# EMS_esp32_LoRa.net
KiCad netlist of a schematic drawn in EAGLE
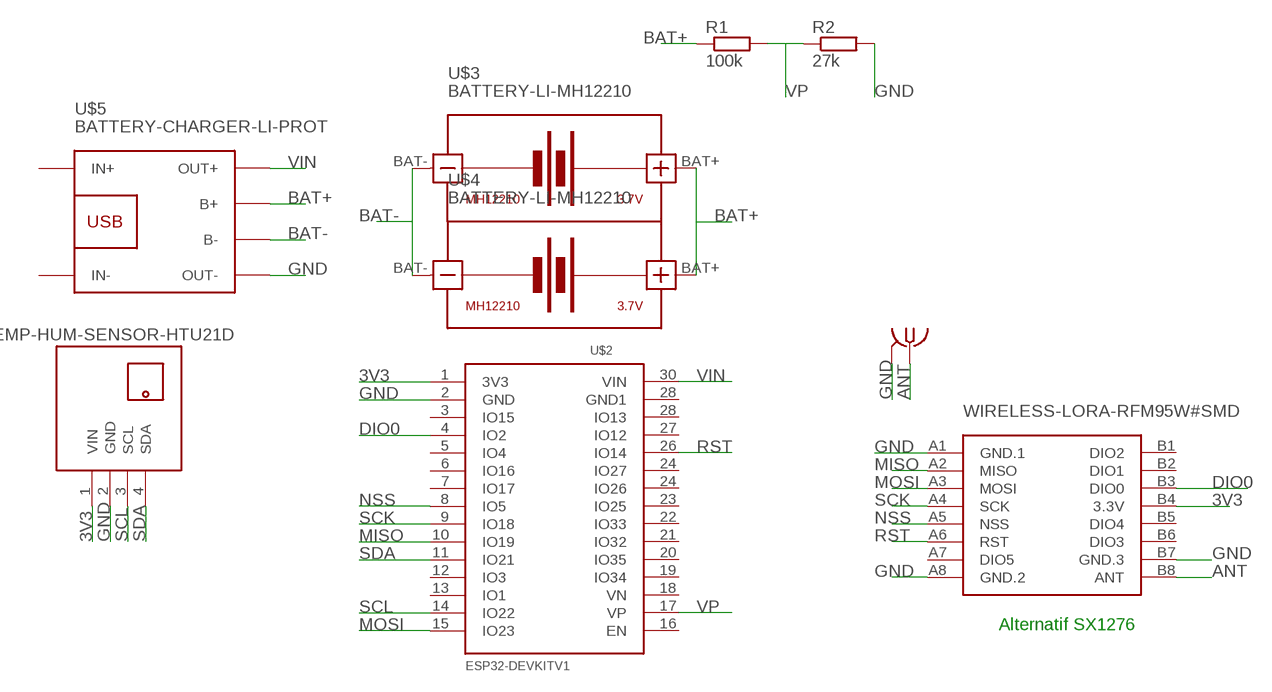
[diagram p0: schematic, sheet 1]

(export (version "E")
  (design (tool "Eeschema 10.0.6"))
  (components
    (comp (ref "R1")
      (value "100k")
      (footprint "eagle-import:0204_7")
      (libsource (lib "eagle-import") (part "R-EU_0204/7"))
    )
    (comp (ref "R2")
      (value "27k")
      (footprint "eagle-import:0204_7")
      (libsource (lib "eagle-import") (part "R-EU_0204/7"))
    )
    (comp (ref "U$1")
      (value "WIRELESS-LORA-RFM95W#SMD")
      (footprint "eagle-import:WIRELESS-LORA-RFM95W#SMD")
      (libsource (lib "eagle-import") (part "WIRELESS-LORA-RFM95W#SMD"))
    )
    (comp (ref "U$2")
      (value "ESP32DEVKITV1")
      (footprint "eagle-import:ESP32-DEVKITV1")
      (libsource (lib "eagle-import") (part "ESP32DEVKITV1"))
    )
    (comp (ref "U$3")
      (value "BATTERY-LI-MH12210")
      (footprint "eagle-import:BATTERY-LI-MH12210")
      (libsource (lib "eagle-import") (part "BATTERY-LI-MH12210"))
    )
    (comp (ref "U$4")
      (value "BATTERY-LI-MH12210")
      (footprint "eagle-import:BATTERY-LI-MH12210")
      (libsource (lib "eagle-import") (part "BATTERY-LI-MH12210"))
    )
    (comp (ref "U$5")
      (value "BATTERY-CHARGER-LI-PROT")
      (footprint "eagle-import:BATTERY-CHARGER-LI-PROT")
      (libsource (lib "eagle-import") (part "BATTERY-CHARGER-LI-PROT"))
    )
    (comp (ref "U$6")
      (value "TEMP-HUM-SENSOR-HTU21D")
      (footprint "eagle-import:TEMP-HUM-SENSOR-HTU21D")
      (libsource (lib "eagle-import") (part "TEMP-HUM-SENSOR-HTU21D"))
    )
    (comp (ref "X1")
      (value "SMA-142-0701-801/806")
      (footprint "eagle-import:J502-ND-142-0701-801_806")
      (fields (field (name "MF") "JOHNSON COMPONENTS") (field (name "MPN") "142-0701-801"))
      (libsource (lib "eagle-import") (part "SMA-142-0701-801/806"))
    )
  )
  (nets
    (net (code "1") (name "/3V3") (class "Default")
      (node (ref "U$1") (pin "B4") (pinfunction "3.3V_B4") (pintype "power_in"))
      (node (ref "U$2") (pin "1") (pinfunction "3V3_1") (pintype "bidirectional"))
      (node (ref "U$6") (pin "1") (pinfunction "VIN_1") (pintype "power_in"))
    )
    (net (code "2") (name "/ANT") (class "Default")
      (node (ref "U$1") (pin "B8") (pinfunction "ANT_B8") (pintype "passive"))
      (node (ref "X1") (pin "1") (pinfunction "1_1") (pintype "passive"))
    )
    (net (code "3") (name "/BAT+") (class "Default")
      (node (ref "R1") (pin "1") (pinfunction "1_1") (pintype "passive"))
      (node (ref "U$3") (pin "BAT+") (pinfunction "BAT+_BAT+") (pintype "power_in"))
      (node (ref "U$4") (pin "BAT+") (pinfunction "BAT+_BAT+") (pintype "power_in"))
      (node (ref "U$5") (pin "B+") (pinfunction "B+_B+") (pintype "bidirectional"))
    )
    (net (code "4") (name "/BAT-") (class "Default")
      (node (ref "U$3") (pin "BAT-") (pinfunction "BAT-_BAT-") (pintype "power_in"))
      (node (ref "U$4") (pin "BAT-") (pinfunction "BAT-_BAT-") (pintype "power_in"))
      (node (ref "U$5") (pin "B-") (pinfunction "B-_B-") (pintype "bidirectional"))
    )
    (net (code "5") (name "/DIO0") (class "Default")
      (node (ref "U$1") (pin "B3") (pinfunction "DIO0_B3") (pintype "bidirectional"))
      (node (ref "U$2") (pin "4") (pinfunction "IO2_4") (pintype "bidirectional"))
    )
    (net (code "6") (name "/GND") (class "Default")
      (node (ref "R2") (pin "2") (pinfunction "2_2") (pintype "passive"))
      (node (ref "U$1") (pin "A1") (pinfunction "GND.1_A1") (pintype "power_in"))
      (node (ref "U$1") (pin "A8") (pinfunction "GND.2_A8") (pintype "power_in"))
      (node (ref "U$1") (pin "B7") (pinfunction "GND.3_B7") (pintype "power_in"))
      (node (ref "U$2") (pin "2") (pinfunction "GND_2") (pintype "bidirectional"))
      (node (ref "U$5") (pin "OUT-") (pinfunction "OUT-_OUT-") (pintype "bidirectional"))
      (node (ref "U$6") (pin "2") (pinfunction "GND_2") (pintype "power_in"))
      (node (ref "X1") (pin "G@1") (pinfunction "2_G@1") (pintype "passive"))
      (node (ref "X1") (pin "G@2") (pinfunction "2_G@2") (pintype "passive"))
      (node (ref "X1") (pin "G@3") (pinfunction "2_G@3") (pintype "passive"))
      (node (ref "X1") (pin "G@4") (pinfunction "2_G@4") (pintype "passive"))
    )
    (net (code "7") (name "/MISO") (class "Default")
      (node (ref "U$1") (pin "A2") (pinfunction "MISO_A2") (pintype "bidirectional"))
      (node (ref "U$2") (pin "10") (pinfunction "IO19_10") (pintype "bidirectional"))
    )
    (net (code "8") (name "/MOSI") (class "Default")
      (node (ref "U$1") (pin "A3") (pinfunction "MOSI_A3") (pintype "bidirectional"))
      (node (ref "U$2") (pin "15") (pinfunction "IO23_15") (pintype "bidirectional"))
    )
    (net (code "9") (name "/NSS") (class "Default")
      (node (ref "U$1") (pin "A5") (pinfunction "NSS_A5") (pintype "bidirectional"))
      (node (ref "U$2") (pin "8") (pinfunction "IO5_8") (pintype "bidirectional"))
    )
    (net (code "10") (name "/RST") (class "Default")
      (node (ref "U$1") (pin "A6") (pinfunction "RST_A6") (pintype "bidirectional"))
      (node (ref "U$2") (pin "26") (pinfunction "IO14_26") (pintype "bidirectional"))
    )
    (net (code "11") (name "/SCK") (class "Default")
      (node (ref "U$1") (pin "A4") (pinfunction "SCK_A4") (pintype "bidirectional"))
      (node (ref "U$2") (pin "9") (pinfunction "IO18_9") (pintype "bidirectional"))
    )
    (net (code "12") (name "/SCL") (class "Default")
      (node (ref "U$2") (pin "14") (pinfunction "IO22_14") (pintype "bidirectional"))
      (node (ref "U$6") (pin "3") (pinfunction "SCL_3") (pintype "bidirectional"))
    )
    (net (code "13") (name "/SDA") (class "Default")
      (node (ref "U$2") (pin "11") (pinfunction "IO21_11") (pintype "bidirectional"))
      (node (ref "U$6") (pin "4") (pinfunction "SDA_4") (pintype "bidirectional"))
    )
    (net (code "14") (name "/VIN") (class "Default")
      (node (ref "U$2") (pin "30") (pinfunction "VIN_30") (pintype "bidirectional"))
      (node (ref "U$5") (pin "OUT+") (pinfunction "OUT+_OUT+") (pintype "bidirectional"))
    )
    (net (code "15") (name "/VP") (class "Default")
      (node (ref "R1") (pin "2") (pinfunction "2_2") (pintype "passive"))
      (node (ref "R2") (pin "1") (pinfunction "1_1") (pintype "passive"))
      (node (ref "U$2") (pin "17") (pinfunction "VP_17") (pintype "bidirectional"))
    )
    (net (code "16") (name "unconnected-(U$1-DIO1-PadB2)") (class "Default")
      (node (ref "U$1") (pin "B2") (pinfunction "DIO1_B2") (pintype "bidirectional"))
    )
    (net (code "17") (name "unconnected-(U$1-DIO2-PadB1)") (class "Default")
      (node (ref "U$1") (pin "B1") (pinfunction "DIO2_B1") (pintype "bidirectional"))
    )
    (net (code "18") (name "unconnected-(U$1-DIO3-PadB6)") (class "Default")
      (node (ref "U$1") (pin "B6") (pinfunction "DIO3_B6") (pintype "bidirectional"))
    )
    (net (code "19") (name "unconnected-(U$1-DIO4-PadB5)") (class "Default")
      (node (ref "U$1") (pin "B5") (pinfunction "DIO4_B5") (pintype "bidirectional"))
    )
    (net (code "20") (name "unconnected-(U$1-DIO5-PadA7)") (class "Default")
      (node (ref "U$1") (pin "A7") (pinfunction "DIO5_A7") (pintype "bidirectional"))
    )
    (net (code "21") (name "unconnected-(U$2-EN-Pad16)") (class "Default")
      (node (ref "U$2") (pin "16") (pinfunction "EN_16") (pintype "bidirectional"))
    )
    (net (code "22") (name "unconnected-(U$2-GND1-Pad28)") (class "Default")
      (node (ref "U$2") (pin "28") (pinfunction "GND1_28") (pintype "bidirectional"))
    )
    (net (code "23") (name "unconnected-(U$2-IO1-Pad13)") (class "Default")
      (node (ref "U$2") (pin "13") (pinfunction "IO1_13") (pintype "bidirectional"))
    )
    (net (code "24") (name "unconnected-(U$2-IO3-Pad12)") (class "Default")
      (node (ref "U$2") (pin "12") (pinfunction "IO3_12") (pintype "bidirectional"))
    )
    (net (code "25") (name "unconnected-(U$2-IO4-Pad5)") (class "Default")
      (node (ref "U$2") (pin "5") (pinfunction "IO4_5") (pintype "bidirectional"))
    )
    (net (code "26") (name "unconnected-(U$2-IO12-Pad27)") (class "Default")
      (node (ref "U$2") (pin "27") (pinfunction "IO12_27") (pintype "bidirectional"))
    )
    (net (code "27") (name "unconnected-(U$2-IO13-Pad28)") (class "Default")
      (node (ref "U$2") (pin "28") (pinfunction "IO13_28") (pintype "bidirectional"))
    )
    (net (code "28") (name "unconnected-(U$2-IO15-Pad3)") (class "Default")
      (node (ref "U$2") (pin "3") (pinfunction "IO15_3") (pintype "bidirectional"))
    )
    (net (code "29") (name "unconnected-(U$2-IO16-Pad6)") (class "Default")
      (node (ref "U$2") (pin "6") (pinfunction "IO16_6") (pintype "bidirectional"))
    )
    (net (code "30") (name "unconnected-(U$2-IO17-Pad7)") (class "Default")
      (node (ref "U$2") (pin "7") (pinfunction "IO17_7") (pintype "bidirectional"))
    )
    (net (code "31") (name "unconnected-(U$2-IO25-Pad23)") (class "Default")
      (node (ref "U$2") (pin "23") (pinfunction "IO25_23") (pintype "bidirectional"))
    )
    (net (code "32") (name "unconnected-(U$2-IO26-Pad24)") (class "Default")
      (node (ref "U$2") (pin "24") (pinfunction "IO26_24") (pintype "bidirectional"))
    )
    (net (code "33") (name "unconnected-(U$2-IO27-Pad24)") (class "Default")
      (node (ref "U$2") (pin "24") (pinfunction "IO27_24") (pintype "bidirectional"))
    )
    (net (code "34") (name "unconnected-(U$2-IO32-Pad21)") (class "Default")
      (node (ref "U$2") (pin "21") (pinfunction "IO32_21") (pintype "bidirectional"))
    )
    (net (code "35") (name "unconnected-(U$2-IO33-Pad22)") (class "Default")
      (node (ref "U$2") (pin "22") (pinfunction "IO33_22") (pintype "bidirectional"))
    )
    (net (code "36") (name "unconnected-(U$2-IO34-Pad19)") (class "Default")
      (node (ref "U$2") (pin "19") (pinfunction "IO34_19") (pintype "bidirectional"))
    )
    (net (code "37") (name "unconnected-(U$2-IO35-Pad20)") (class "Default")
      (node (ref "U$2") (pin "20") (pinfunction "IO35_20") (pintype "bidirectional"))
    )
    (net (code "38") (name "unconnected-(U$2-VN-Pad18)") (class "Default")
      (node (ref "U$2") (pin "18") (pinfunction "VN_18") (pintype "bidirectional"))
    )
    (net (code "39") (name "unconnected-(U$5-PadIN+)") (class "Default")
      (node (ref "U$5") (pin "IN+") (pinfunction "IN+_IN+") (pintype "bidirectional"))
    )
    (net (code "40") (name "unconnected-(U$5-PadIN-)") (class "Default")
      (node (ref "U$5") (pin "IN-") (pinfunction "IN-_IN-") (pintype "bidirectional"))
    )
  )
)
